# fonte_schema.net
KiCad netlist of a schematic drawn in EAGLE
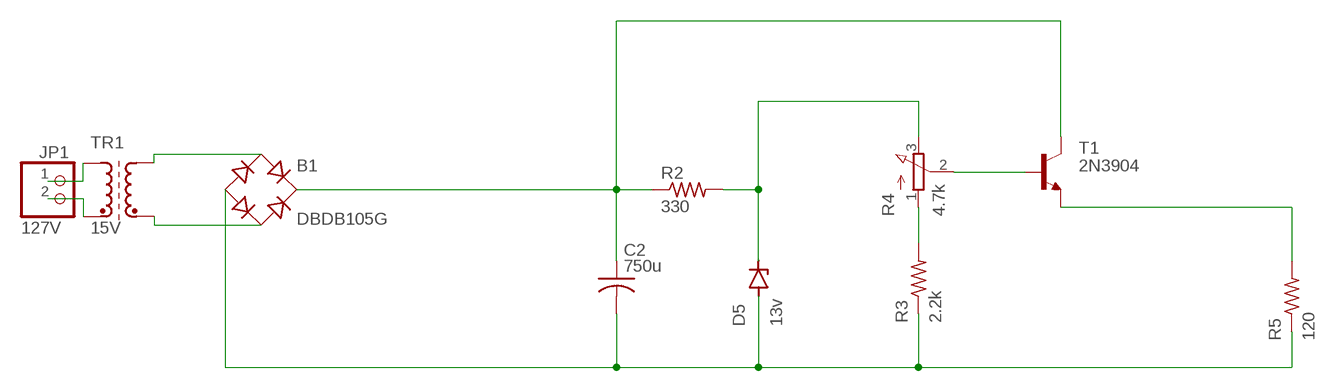
[diagram p0: schematic, sheet 1]

(export (version "E")
  (design (tool "Eeschema 10.0.6"))
  (components
    (comp (ref "B1")
      (value "DBDB105G")
      (footprint "eagle-import:DB")
      (libsource (lib "eagle-import") (part "DB?GDB105"))
    )
    (comp (ref "C2")
      (value "750u")
      (footprint "eagle-import:C0805")
      (libsource (lib "eagle-import") (part "C-USC0805"))
    )
    (comp (ref "D5")
      (value "13v")
      (footprint "eagle-import:DO35Z10")
      (fields (field (name "SPICEPREFIX") "D"))
      (libsource (lib "eagle-import") (part "ZENER-DIODEDO35Z10"))
    )
    (comp (ref "JP1")
      (value "127V")
      (footprint "eagle-import:1X02")
      (fields (field (name "SPICEPREFIX") "H"))
      (libsource (lib "eagle-import") (part "PINHD-1X2"))
    )
    (comp (ref "R2")
      (value "330")
      (footprint "eagle-import:R0805")
      (libsource (lib "eagle-import") (part "R-US_R0805"))
    )
    (comp (ref "R3")
      (value "2.2k")
      (footprint "eagle-import:R0805")
      (libsource (lib "eagle-import") (part "R-US_R0805"))
    )
    (comp (ref "R4")
      (value "4.7k")
      (footprint "eagle-import:3RP_1610N")
      (fields (field (name "SPICEPREFIX") "J"))
      (libsource (lib "eagle-import") (part "3RP/1610N"))
    )
    (comp (ref "R5")
      (value "120")
      (footprint "eagle-import:R0805")
      (libsource (lib "eagle-import") (part "R-US_R0805"))
    )
    (comp (ref "T1")
      (value "2N3904")
      (footprint "eagle-import:TO92")
      (fields (field (name "SPICEPREFIX") "J"))
      (libsource (lib "eagle-import") (part "2N3904"))
    )
    (comp (ref "TR1")
      (value "15V")
      (footprint "eagle-import:SM-T4")
      (fields (field (name "SPICEPREFIX") "T"))
      (libsource (lib "eagle-import") (part "SM-T4"))
    )
  )
  (nets
    (net (code "1") (name "Net-(B1-Pad-)") (class "Default")
      (node (ref "B1") (pin "-") (pinfunction "-_-") (pintype "passive"))
      (node (ref "C2") (pin "2") (pinfunction "2_2") (pintype "passive"))
      (node (ref "D5") (pin "A") (pinfunction "A_A") (pintype "passive"))
      (node (ref "R3") (pin "1") (pinfunction "1_1") (pintype "passive"))
      (node (ref "R5") (pin "1") (pinfunction "1_1") (pintype "passive"))
    )
    (net (code "2") (name "Net-(R4-A)") (class "Default")
      (node (ref "R3") (pin "2") (pinfunction "2_2") (pintype "passive"))
      (node (ref "R4") (pin "1") (pinfunction "A_1") (pintype "passive"))
    )
    (net (code "3") (name "Net-(R4-E)") (class "Default")
      (node (ref "D5") (pin "C") (pinfunction "C_C") (pintype "passive"))
      (node (ref "R2") (pin "2") (pinfunction "2_2") (pintype "passive"))
      (node (ref "R4") (pin "3") (pinfunction "E_3") (pintype "passive"))
    )
    (net (code "4") (name "Net-(R4-S)") (class "Default")
      (node (ref "R4") (pin "2") (pinfunction "S_2") (pintype "passive"))
      (node (ref "T1") (pin "2") (pinfunction "B_2") (pintype "passive"))
    )
    (net (code "5") (name "Net-(T1-C)") (class "Default")
      (node (ref "B1") (pin "+") (pinfunction "+_+") (pintype "passive"))
      (node (ref "C2") (pin "1") (pinfunction "1_1") (pintype "passive"))
      (node (ref "R2") (pin "1") (pinfunction "1_1") (pintype "passive"))
      (node (ref "T1") (pin "1") (pinfunction "C_1") (pintype "passive"))
    )
    (net (code "6") (name "Net-(T1-E)") (class "Default")
      (node (ref "R5") (pin "2") (pinfunction "2_2") (pintype "passive"))
      (node (ref "T1") (pin "3") (pinfunction "E_3") (pintype "passive"))
    )
    (net (code "7") (name "Net-(TR1-A1)") (class "Default")
      (node (ref "JP1") (pin "1") (pinfunction "1_1") (pintype "passive"))
      (node (ref "TR1") (pin "1") (pinfunction "A1_1") (pintype "passive"))
    )
    (net (code "8") (name "Net-(TR1-A2)") (class "Default")
      (node (ref "B1") (pin "AC1") (pinfunction "AC1_AC1") (pintype "passive"))
      (node (ref "TR1") (pin "5") (pinfunction "A2_5") (pintype "passive"))
    )
    (net (code "9") (name "Net-(TR1-E1)") (class "Default")
      (node (ref "JP1") (pin "2") (pinfunction "2_2") (pintype "passive"))
      (node (ref "TR1") (pin "2") (pinfunction "E1_2") (pintype "passive"))
    )
    (net (code "10") (name "Net-(TR1-E2)") (class "Default")
      (node (ref "B1") (pin "AC2") (pinfunction "AC2_AC2") (pintype "passive"))
      (node (ref "TR1") (pin "4") (pinfunction "E2_4") (pintype "passive"))
    )
  )
)
